# light_connect.net
KiCad netlist of a schematic drawn in EAGLE
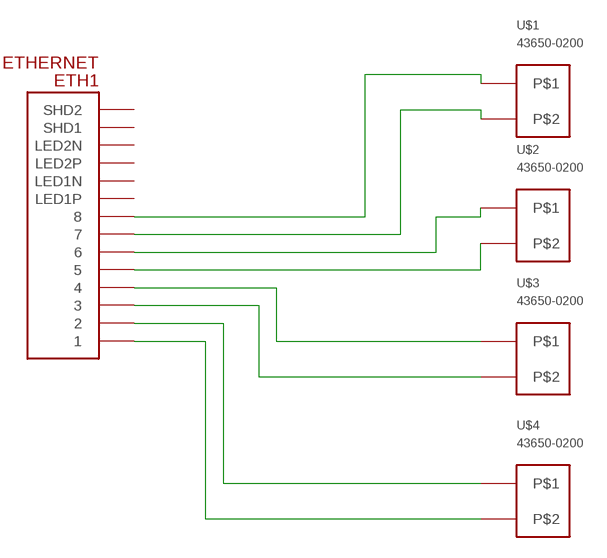
[diagram p0: schematic, sheet 1]

(export (version "E")
  (design (tool "Eeschema 10.0.6"))
  (components
    (comp (ref "ETH1")
      (value "ETHERNET")
      (footprint "eagle-import:A122645-ND")
      (libsource (lib "eagle-import") (part "ETHERNET"))
    )
    (comp (ref "U$1")
      (value "43650-0200")
      (footprint "eagle-import:43650-0200")
      (libsource (lib "eagle-import") (part "43650-0200"))
    )
    (comp (ref "U$2")
      (value "43650-0200")
      (footprint "eagle-import:43650-0200")
      (libsource (lib "eagle-import") (part "43650-0200"))
    )
    (comp (ref "U$3")
      (value "43650-0200")
      (footprint "eagle-import:43650-0200")
      (libsource (lib "eagle-import") (part "43650-0200"))
    )
    (comp (ref "U$4")
      (value "43650-0200")
      (footprint "eagle-import:43650-0200")
      (libsource (lib "eagle-import") (part "43650-0200"))
    )
  )
  (nets
    (net (code "1") (name "Net-(ETH1-1)") (class "Default")
      (node (ref "ETH1") (pin "P$1") (pinfunction "1_P$1") (pintype "bidirectional"))
      (node (ref "U$4") (pin "P$1") (pinfunction "P$2_P$1") (pintype "bidirectional"))
    )
    (net (code "2") (name "Net-(ETH1-2)") (class "Default")
      (node (ref "ETH1") (pin "P$2") (pinfunction "2_P$2") (pintype "bidirectional"))
      (node (ref "U$4") (pin "P$2") (pinfunction "P$1_P$2") (pintype "bidirectional"))
    )
    (net (code "3") (name "Net-(ETH1-3)") (class "Default")
      (node (ref "ETH1") (pin "P$3") (pinfunction "3_P$3") (pintype "bidirectional"))
      (node (ref "U$3") (pin "P$1") (pinfunction "P$2_P$1") (pintype "bidirectional"))
    )
    (net (code "4") (name "Net-(ETH1-4)") (class "Default")
      (node (ref "ETH1") (pin "P$4") (pinfunction "4_P$4") (pintype "bidirectional"))
      (node (ref "U$3") (pin "P$2") (pinfunction "P$1_P$2") (pintype "bidirectional"))
    )
    (net (code "5") (name "Net-(ETH1-5)") (class "Default")
      (node (ref "ETH1") (pin "P$5") (pinfunction "5_P$5") (pintype "bidirectional"))
      (node (ref "U$2") (pin "P$1") (pinfunction "P$2_P$1") (pintype "bidirectional"))
    )
    (net (code "6") (name "Net-(ETH1-6)") (class "Default")
      (node (ref "ETH1") (pin "P$6") (pinfunction "6_P$6") (pintype "bidirectional"))
      (node (ref "U$2") (pin "P$2") (pinfunction "P$1_P$2") (pintype "bidirectional"))
    )
    (net (code "7") (name "Net-(ETH1-7)") (class "Default")
      (node (ref "ETH1") (pin "P$7") (pinfunction "7_P$7") (pintype "bidirectional"))
      (node (ref "U$1") (pin "P$1") (pinfunction "P$2_P$1") (pintype "bidirectional"))
    )
    (net (code "8") (name "Net-(ETH1-8)") (class "Default")
      (node (ref "ETH1") (pin "P$8") (pinfunction "8_P$8") (pintype "bidirectional"))
      (node (ref "U$1") (pin "P$2") (pinfunction "P$1_P$2") (pintype "bidirectional"))
    )
    (net (code "9") (name "unconnected-(ETH1-LED1N-PadP$9)") (class "Default")
      (node (ref "ETH1") (pin "P$9") (pinfunction "LED1N_P$9") (pintype "bidirectional"))
    )
    (net (code "10") (name "unconnected-(ETH1-LED1P-PadP$10)") (class "Default")
      (node (ref "ETH1") (pin "P$10") (pinfunction "LED1P_P$10") (pintype "bidirectional"))
    )
    (net (code "11") (name "unconnected-(ETH1-LED2N-PadP$11)") (class "Default")
      (node (ref "ETH1") (pin "P$11") (pinfunction "LED2N_P$11") (pintype "bidirectional"))
    )
    (net (code "12") (name "unconnected-(ETH1-LED2P-PadP$12)") (class "Default")
      (node (ref "ETH1") (pin "P$12") (pinfunction "LED2P_P$12") (pintype "bidirectional"))
    )
    (net (code "13") (name "unconnected-(ETH1-SHD1-PadP$13)") (class "Default")
      (node (ref "ETH1") (pin "P$13") (pinfunction "SHD1_P$13") (pintype "bidirectional"))
    )
    (net (code "14") (name "unconnected-(ETH1-SHD2-PadP$14)") (class "Default")
      (node (ref "ETH1") (pin "P$14") (pinfunction "SHD2_P$14") (pintype "bidirectional"))
    )
  )
)
